# power.net
KiCad netlist of a schematic drawn in Altium Designer
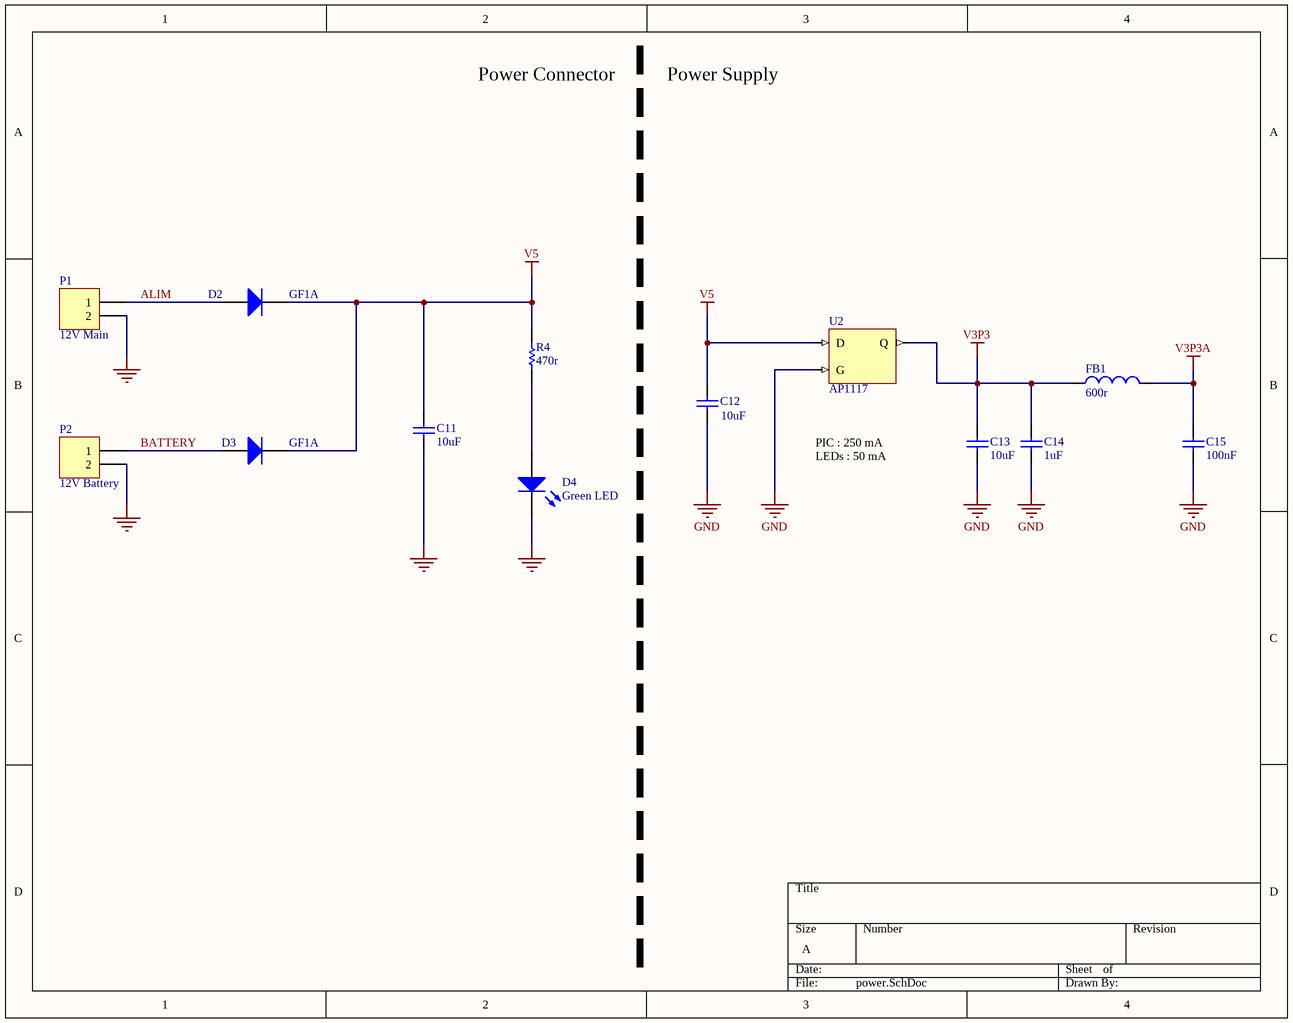
[diagram p0: power.SchDoc]

(export (version "E")
  (design (tool "Eeschema 10.0.6"))
  (components
    (comp (ref "C11")
      (value "10uF")
      (footprint "CAPC2012N")
      (description "Capacitor")
      (fields (field (name "PUBLISHER") "Altium Limited"))
      (libsource (lib "Miscellaneous Devices") (part "Cap"))
    )
    (comp (ref "C12")
      (value "10uF")
      (footprint "CAPC2012N")
      (description "Capacitor")
      (fields (field (name "PUBLISHER") "Altium Limited"))
      (libsource (lib "Miscellaneous Devices") (part "Cap"))
    )
    (comp (ref "C13")
      (value "10uF")
      (footprint "CAPC2012N")
      (description "Capacitor")
      (fields (field (name "PUBLISHER") "Altium Limited"))
      (libsource (lib "Miscellaneous Devices") (part "Cap"))
    )
    (comp (ref "C14")
      (value "1uF")
      (footprint "CAPC1608N")
      (description "Capacitor")
      (fields (field (name "PUBLISHER") "Altium Limited"))
      (libsource (lib "Miscellaneous Devices") (part "Cap"))
    )
    (comp (ref "C15")
      (value "100nF")
      (footprint "RAD-0.3")
      (description "Capacitor")
      (fields (field (name "PUBLISHER") "Altium Limited"))
      (libsource (lib "Miscellaneous Devices") (part "Cap"))
    )
    (comp (ref "D2")
      (value "GF1A")
      (footprint "SMA/DO-214AC_21")
      (description "Default Diode")
      (fields (field (name "PUBLISHER") "Altium Limited"))
      (libsource (lib "Miscellaneous Devices") (part "Diode"))
    )
    (comp (ref "D3")
      (value "GF1A")
      (footprint "SMA/DO-214AC_21")
      (description "Default Diode")
      (fields (field (name "PUBLISHER") "Altium Limited"))
      (libsource (lib "Miscellaneous Devices") (part "Diode"))
    )
    (comp (ref "D4")
      (value "Green LED")
      (footprint "LED 0805")
      (description "Typical RED, GREEN, YELLOW, AMBER GaAs LED")
      (fields (field (name "PUBLISHER") "Altium Limited"))
      (libsource (lib "Miscellaneous Devices") (part "LED2"))
    )
    (comp (ref "FB1")
      (value "600r")
      (footprint "INDC1608AN")
      (description "Inductor")
      (fields (field (name "PUBLISHER") "Altium Limited"))
      (libsource (lib "Miscellaneous Devices") (part "Inductor"))
    )
    (comp (ref "P1")
      (value "12V Main")
      (footprint "PHOENIX_1985195")
      (description "Header, 2-Pin")
      (fields (field (name "PUBLISHER") "Altium Limited"))
      (libsource (lib "Miscellaneous Connectors") (part "Header 2"))
    )
    (comp (ref "P2")
      (value "12V Battery")
      (footprint "PHOENIX_1985195")
      (description "Header, 2-Pin")
      (fields (field (name "PUBLISHER") "Altium Limited"))
      (libsource (lib "Miscellaneous Connectors") (part "Header 2"))
    )
    (comp (ref "R4")
      (value "470r")
      (footprint "RESC1608N")
      (description "Resistor")
      (fields (field (name "PUBLISHER") "Altium Limited"))
      (libsource (lib "Miscellaneous Devices") (part "Res1"))
    )
    (comp (ref "U2")
      (value "AP1117")
      (footprint "TD03B_N")
      (description "1A LDO, 18V input, DPAK")
      (fields (field (name "PUBLISHER") "Altium Limited"))
      (libsource (lib "FPGA Generic") (part "LD"))
    )
  )
  (nets
    (net (code "1") (name "/ALIM") (class "Default")
      (node (ref "D2") (pin "1") (pinfunction "A_1") (pintype "passive"))
      (node (ref "P1") (pin "1") (pinfunction "1_1") (pintype "passive"))
    )
    (net (code "2") (name "/BATTERY") (class "Default")
      (node (ref "D3") (pin "1") (pinfunction "A_1") (pintype "passive"))
      (node (ref "P2") (pin "1") (pinfunction "1_1") (pintype "passive"))
    )
    (net (code "3") (name "GND") (class "Default")
      (node (ref "C11") (pin "1") (pinfunction "1_1") (pintype "passive"))
      (node (ref "C12") (pin "1") (pinfunction "1_1") (pintype "passive"))
      (node (ref "C13") (pin "1") (pinfunction "1_1") (pintype "passive"))
      (node (ref "C14") (pin "1") (pinfunction "1_1") (pintype "passive"))
      (node (ref "C15") (pin "1") (pinfunction "1_1") (pintype "passive"))
      (node (ref "D4") (pin "2") (pinfunction "K_2") (pintype "passive"))
      (node (ref "P1") (pin "2") (pinfunction "2_2") (pintype "passive"))
      (node (ref "P2") (pin "2") (pinfunction "2_2") (pintype "passive"))
      (node (ref "U2") (pin "G") (pinfunction "G_G") (pintype "input"))
    )
    (net (code "4") (name "Net-(D4-A)") (class "Default")
      (node (ref "D4") (pin "1") (pinfunction "A_1") (pintype "passive"))
      (node (ref "R4") (pin "1") (pinfunction "1_1") (pintype "passive"))
    )
    (net (code "5") (name "V3P3") (class "Default")
      (node (ref "C13") (pin "2") (pinfunction "2_2") (pintype "passive"))
      (node (ref "C14") (pin "2") (pinfunction "2_2") (pintype "passive"))
      (node (ref "FB1") (pin "1") (pinfunction "1_1") (pintype "passive"))
      (node (ref "U2") (pin "Q") (pinfunction "Q_Q") (pintype "output"))
    )
    (net (code "6") (name "V3P3A") (class "Default")
      (node (ref "C15") (pin "2") (pinfunction "2_2") (pintype "passive"))
      (node (ref "FB1") (pin "2") (pinfunction "2_2") (pintype "passive"))
    )
    (net (code "7") (name "V5") (class "Default")
      (node (ref "C11") (pin "2") (pinfunction "2_2") (pintype "passive"))
      (node (ref "C12") (pin "2") (pinfunction "2_2") (pintype "passive"))
      (node (ref "D2") (pin "2") (pinfunction "K_2") (pintype "passive"))
      (node (ref "D3") (pin "2") (pinfunction "K_2") (pintype "passive"))
      (node (ref "R4") (pin "2") (pinfunction "2_2") (pintype "passive"))
      (node (ref "U2") (pin "D") (pinfunction "D_D") (pintype "input"))
    )
  )
)
